# LEDmatrixboardV1_2_4.net
KiCad netlist of a schematic drawn in EAGLE
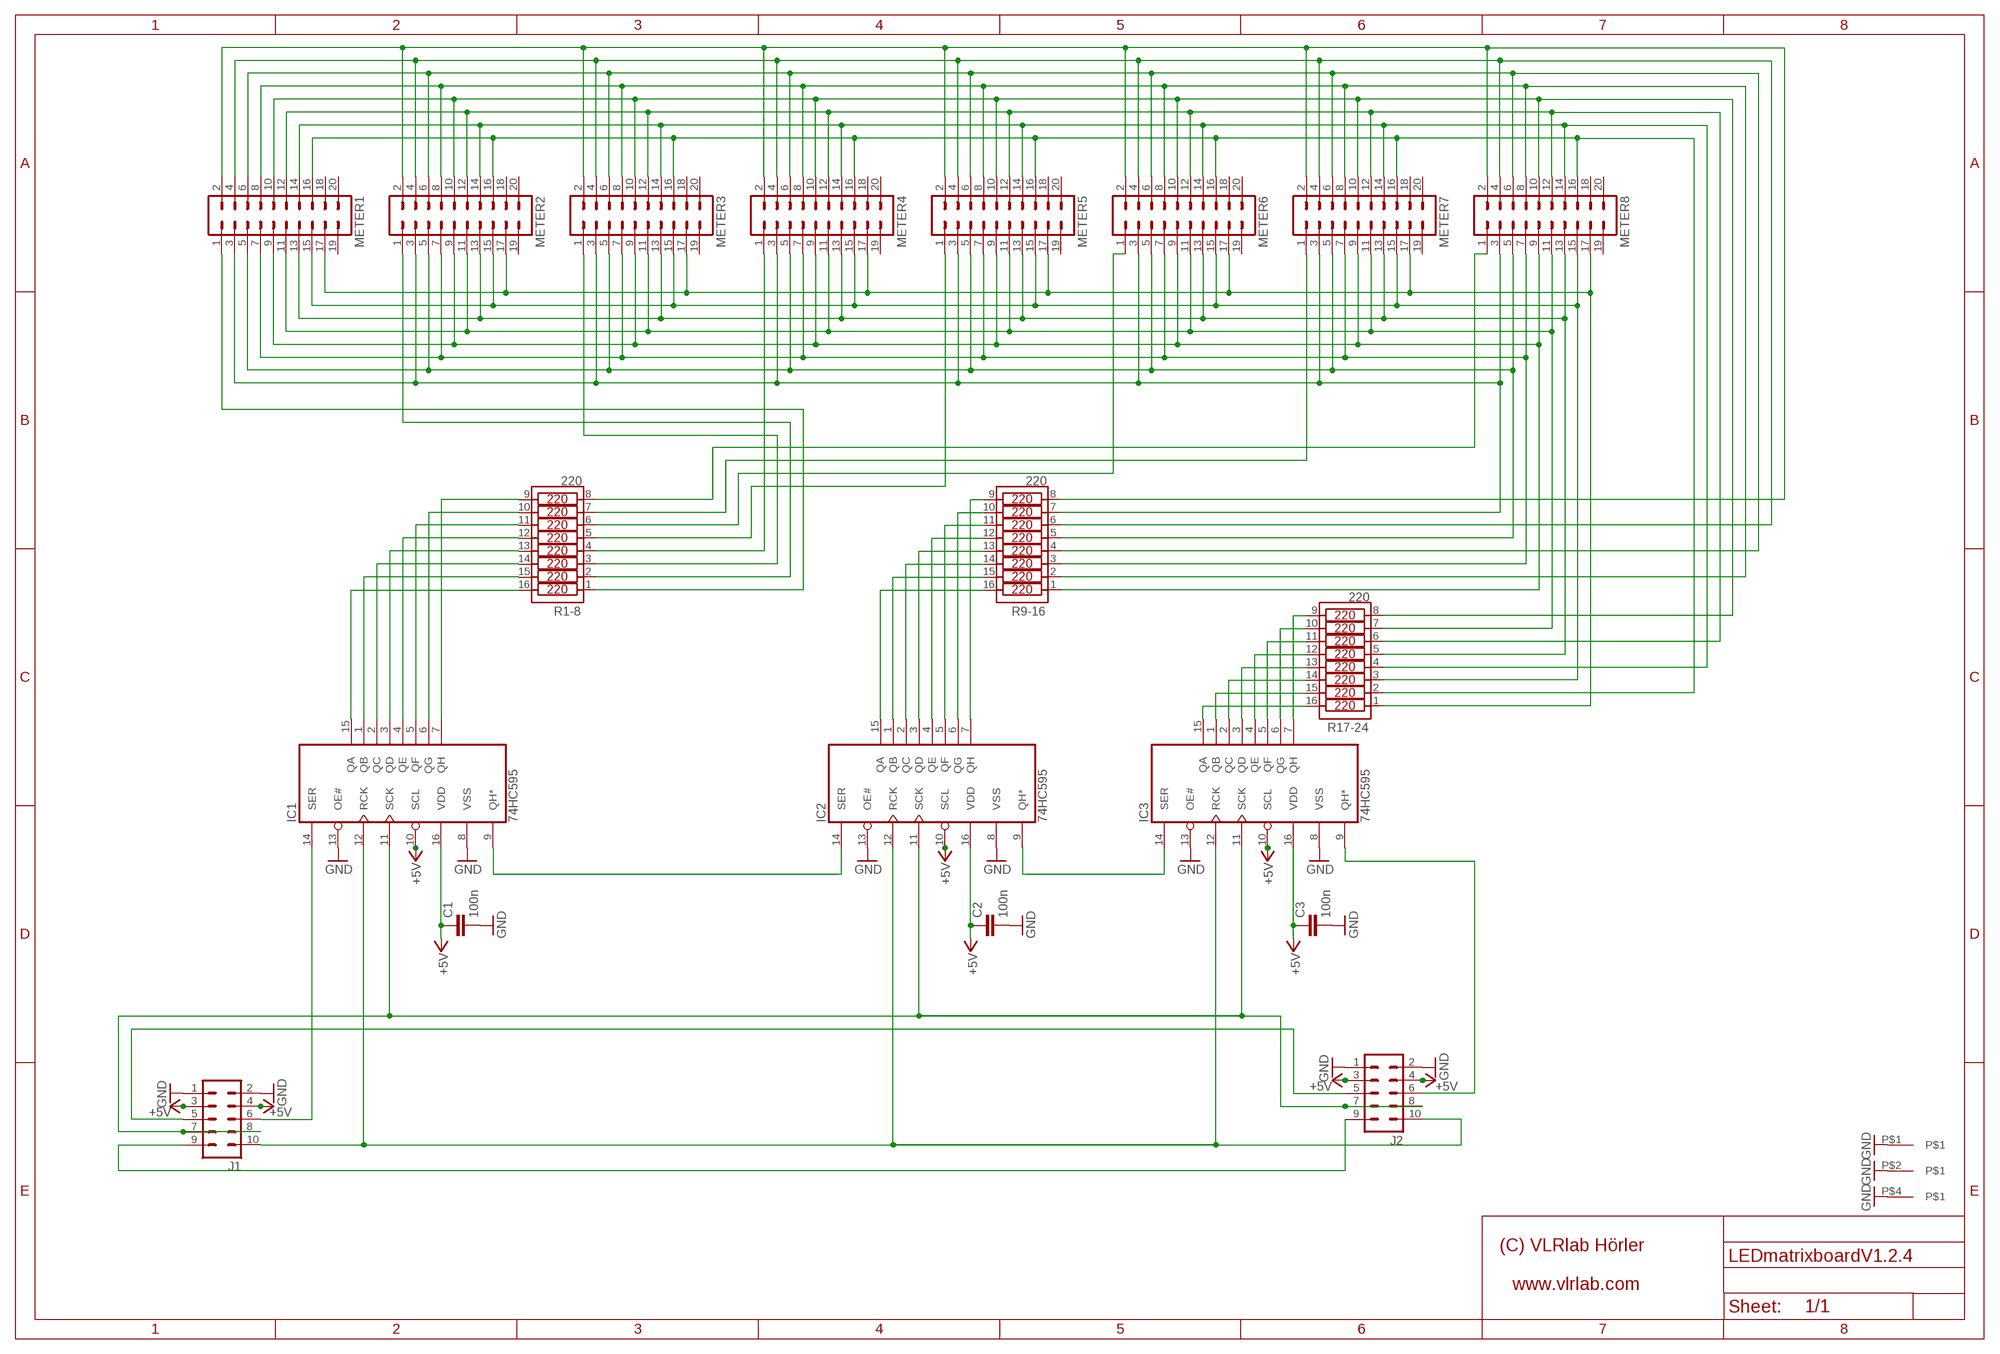
[diagram p0: schematic, sheet 1]

(export (version "E")
  (design (tool "Eeschema 10.0.6"))
  (components
    (comp (ref "C1")
      (value "100n")
      (footprint "eagle-import:C025-030X050")
      (libsource (lib "eagle-import") (part "C-EU025-030X050"))
    )
    (comp (ref "C2")
      (value "100n")
      (footprint "eagle-import:C025-030X050")
      (libsource (lib "eagle-import") (part "C-EU025-030X050"))
    )
    (comp (ref "C3")
      (value "100n")
      (footprint "eagle-import:C025-030X050")
      (libsource (lib "eagle-import") (part "C-EU025-030X050"))
    )
    (comp (ref "IC1")
      (value "74HC595")
      (footprint "eagle-import:SO16D")
      (libsource (lib "eagle-import") (part "595-541-165-uln2803_74HC595SO16D"))
    )
    (comp (ref "IC2")
      (value "74HC595")
      (footprint "eagle-import:SO16D")
      (libsource (lib "eagle-import") (part "595-541-165-uln2803_74HC595SO16D"))
    )
    (comp (ref "IC3")
      (value "74HC595")
      (footprint "eagle-import:SO16D")
      (libsource (lib "eagle-import") (part "595-541-165-uln2803_74HC595SO16D"))
    )
    (comp (ref "J1")
      (value "ML10")
      (footprint "eagle-import:ML10")
      (libsource (lib "eagle-import") (part "ML10"))
    )
    (comp (ref "J2")
      (value "ML10")
      (footprint "eagle-import:ML10")
      (libsource (lib "eagle-import") (part "ML10"))
    )
    (comp (ref "METER1")
      (value "ML20")
      (footprint "eagle-import:ML20")
      (libsource (lib "eagle-import") (part "ML20"))
    )
    (comp (ref "METER2")
      (value "ML20")
      (footprint "eagle-import:ML20")
      (libsource (lib "eagle-import") (part "ML20"))
    )
    (comp (ref "METER3")
      (value "ML20")
      (footprint "eagle-import:ML20")
      (libsource (lib "eagle-import") (part "ML20"))
    )
    (comp (ref "METER4")
      (value "ML20")
      (footprint "eagle-import:ML20")
      (libsource (lib "eagle-import") (part "ML20"))
    )
    (comp (ref "METER5")
      (value "ML20")
      (footprint "eagle-import:ML20")
      (libsource (lib "eagle-import") (part "ML20"))
    )
    (comp (ref "METER6")
      (value "ML20")
      (footprint "eagle-import:ML20")
      (libsource (lib "eagle-import") (part "ML20"))
    )
    (comp (ref "METER7")
      (value "ML20")
      (footprint "eagle-import:ML20")
      (libsource (lib "eagle-import") (part "ML20"))
    )
    (comp (ref "METER8")
      (value "ML20")
      (footprint "eagle-import:ML20")
      (libsource (lib "eagle-import") (part "ML20"))
    )
    (comp (ref "R1-8")
      (value "220")
      (footprint "eagle-import:SOIC16W")
      (libsource (lib "eagle-import") (part "4816P-1SOIC16W"))
    )
    (comp (ref "R9-16")
      (value "220")
      (footprint "eagle-import:SOIC16W")
      (libsource (lib "eagle-import") (part "4816P-1SOIC16W"))
    )
    (comp (ref "R17-24")
      (value "220")
      (footprint "eagle-import:SOIC16W")
      (libsource (lib "eagle-import") (part "4816P-1SOIC16W"))
    )
    (comp (ref "U$2")
      (value "MIDIBOX_HALF")
      (footprint "eagle-import:MIDIBOX14X6")
      (libsource (lib "eagle-import") (part "MIDIBOX_HALF"))
    )
  )
  (nets
    (net (code "1") (name "+5V") (class "Default")
      (node (ref "C1") (pin "1") (pinfunction "1_1") (pintype "passive"))
      (node (ref "C2") (pin "1") (pinfunction "1_1") (pintype "passive"))
      (node (ref "C3") (pin "1") (pinfunction "1_1") (pintype "passive"))
      (node (ref "IC1") (pin "10") (pinfunction "SCL_10") (pintype "input"))
      (node (ref "IC1") (pin "16") (pinfunction "VDD_16") (pintype "power_in"))
      (node (ref "IC2") (pin "10") (pinfunction "SCL_10") (pintype "input"))
      (node (ref "IC2") (pin "16") (pinfunction "VDD_16") (pintype "power_in"))
      (node (ref "IC3") (pin "10") (pinfunction "SCL_10") (pintype "input"))
      (node (ref "IC3") (pin "16") (pinfunction "VDD_16") (pintype "power_in"))
      (node (ref "J1") (pin "3") (pinfunction "3_3") (pintype "passive"))
      (node (ref "J1") (pin "4") (pinfunction "4_4") (pintype "passive"))
      (node (ref "J2") (pin "3") (pinfunction "3_3") (pintype "passive"))
      (node (ref "J2") (pin "4") (pinfunction "4_4") (pintype "passive"))
    )
    (net (code "2") (name "GND") (class "Default")
      (node (ref "C1") (pin "2") (pinfunction "2_2") (pintype "passive"))
      (node (ref "C2") (pin "2") (pinfunction "2_2") (pintype "passive"))
      (node (ref "C3") (pin "2") (pinfunction "2_2") (pintype "passive"))
      (node (ref "IC1") (pin "13") (pinfunction "OE#_13") (pintype "input"))
      (node (ref "IC1") (pin "8") (pinfunction "VSS_8") (pintype "power_in"))
      (node (ref "IC2") (pin "13") (pinfunction "OE#_13") (pintype "input"))
      (node (ref "IC2") (pin "8") (pinfunction "VSS_8") (pintype "power_in"))
      (node (ref "IC3") (pin "13") (pinfunction "OE#_13") (pintype "input"))
      (node (ref "IC3") (pin "8") (pinfunction "VSS_8") (pintype "power_in"))
      (node (ref "J1") (pin "1") (pinfunction "1_1") (pintype "passive"))
      (node (ref "J1") (pin "2") (pinfunction "2_2") (pintype "passive"))
      (node (ref "J2") (pin "1") (pinfunction "1_1") (pintype "passive"))
      (node (ref "J2") (pin "2") (pinfunction "2_2") (pintype "passive"))
      (node (ref "U$2") (pin "P$1") (pinfunction "P$1_P$1") (pintype "bidirectional"))
      (node (ref "U$2") (pin "P$2") (pinfunction "P$1_P$2") (pintype "bidirectional"))
      (node (ref "U$2") (pin "P$4") (pinfunction "P$1_P$4") (pintype "bidirectional"))
    )
    (net (code "3") (name "Net-(IC1-QA)") (class "Default")
      (node (ref "IC1") (pin "15") (pinfunction "QA_15") (pintype "tri_state"))
      (node (ref "R1-8") (pin "16") (pinfunction "P$16_16") (pintype "passive"))
    )
    (net (code "4") (name "Net-(IC1-QB)") (class "Default")
      (node (ref "IC1") (pin "1") (pinfunction "QB_1") (pintype "tri_state"))
      (node (ref "R1-8") (pin "15") (pinfunction "P$15_15") (pintype "passive"))
    )
    (net (code "5") (name "Net-(IC1-QC)") (class "Default")
      (node (ref "IC1") (pin "2") (pinfunction "QC_2") (pintype "tri_state"))
      (node (ref "R1-8") (pin "14") (pinfunction "P$14_14") (pintype "passive"))
    )
    (net (code "6") (name "Net-(IC1-QD)") (class "Default")
      (node (ref "IC1") (pin "3") (pinfunction "QD_3") (pintype "tri_state"))
      (node (ref "R1-8") (pin "13") (pinfunction "P$13_13") (pintype "passive"))
    )
    (net (code "7") (name "Net-(IC1-QE)") (class "Default")
      (node (ref "IC1") (pin "4") (pinfunction "QE_4") (pintype "tri_state"))
      (node (ref "R1-8") (pin "12") (pinfunction "P$12_12") (pintype "passive"))
    )
    (net (code "8") (name "Net-(IC1-QF)") (class "Default")
      (node (ref "IC1") (pin "5") (pinfunction "QF_5") (pintype "tri_state"))
      (node (ref "R1-8") (pin "11") (pinfunction "P$11_11") (pintype "passive"))
    )
    (net (code "9") (name "Net-(IC1-QG)") (class "Default")
      (node (ref "IC1") (pin "6") (pinfunction "QG_6") (pintype "tri_state"))
      (node (ref "R1-8") (pin "10") (pinfunction "P$10_10") (pintype "passive"))
    )
    (net (code "10") (name "Net-(IC1-QH)") (class "Default")
      (node (ref "IC1") (pin "7") (pinfunction "QH_7") (pintype "tri_state"))
      (node (ref "R1-8") (pin "9") (pinfunction "P$9_9") (pintype "passive"))
    )
    (net (code "11") (name "Net-(IC1-QH*)") (class "Default")
      (node (ref "IC1") (pin "9") (pinfunction "QH*_9") (pintype "tri_state"))
      (node (ref "IC2") (pin "14") (pinfunction "SER_14") (pintype "input"))
    )
    (net (code "12") (name "Net-(IC1-RCK)") (class "Default")
      (node (ref "IC1") (pin "12") (pinfunction "RCK_12") (pintype "input"))
      (node (ref "IC2") (pin "12") (pinfunction "RCK_12") (pintype "input"))
      (node (ref "IC3") (pin "12") (pinfunction "RCK_12") (pintype "input"))
      (node (ref "J1") (pin "10") (pinfunction "10_10") (pintype "passive"))
      (node (ref "J2") (pin "10") (pinfunction "10_10") (pintype "passive"))
    )
    (net (code "13") (name "Net-(IC1-SCK)") (class "Default")
      (node (ref "IC1") (pin "11") (pinfunction "SCK_11") (pintype "input"))
      (node (ref "IC2") (pin "11") (pinfunction "SCK_11") (pintype "input"))
      (node (ref "IC3") (pin "11") (pinfunction "SCK_11") (pintype "input"))
      (node (ref "J1") (pin "7") (pinfunction "7_7") (pintype "passive"))
      (node (ref "J1") (pin "8") (pinfunction "8_8") (pintype "passive"))
      (node (ref "J2") (pin "7") (pinfunction "7_7") (pintype "passive"))
      (node (ref "J2") (pin "8") (pinfunction "8_8") (pintype "passive"))
    )
    (net (code "14") (name "Net-(IC1-SER)") (class "Default")
      (node (ref "IC1") (pin "14") (pinfunction "SER_14") (pintype "input"))
      (node (ref "J1") (pin "6") (pinfunction "6_6") (pintype "passive"))
    )
    (net (code "15") (name "Net-(IC2-QA)") (class "Default")
      (node (ref "IC2") (pin "15") (pinfunction "QA_15") (pintype "tri_state"))
      (node (ref "R9-16") (pin "16") (pinfunction "P$16_16") (pintype "passive"))
    )
    (net (code "16") (name "Net-(IC2-QB)") (class "Default")
      (node (ref "IC2") (pin "1") (pinfunction "QB_1") (pintype "tri_state"))
      (node (ref "R9-16") (pin "15") (pinfunction "P$15_15") (pintype "passive"))
    )
    (net (code "17") (name "Net-(IC2-QC)") (class "Default")
      (node (ref "IC2") (pin "2") (pinfunction "QC_2") (pintype "tri_state"))
      (node (ref "R9-16") (pin "14") (pinfunction "P$14_14") (pintype "passive"))
    )
    (net (code "18") (name "Net-(IC2-QD)") (class "Default")
      (node (ref "IC2") (pin "3") (pinfunction "QD_3") (pintype "tri_state"))
      (node (ref "R9-16") (pin "13") (pinfunction "P$13_13") (pintype "passive"))
    )
    (net (code "19") (name "Net-(IC2-QE)") (class "Default")
      (node (ref "IC2") (pin "4") (pinfunction "QE_4") (pintype "tri_state"))
      (node (ref "R9-16") (pin "12") (pinfunction "P$12_12") (pintype "passive"))
    )
    (net (code "20") (name "Net-(IC2-QF)") (class "Default")
      (node (ref "IC2") (pin "5") (pinfunction "QF_5") (pintype "tri_state"))
      (node (ref "R9-16") (pin "11") (pinfunction "P$11_11") (pintype "passive"))
    )
    (net (code "21") (name "Net-(IC2-QG)") (class "Default")
      (node (ref "IC2") (pin "6") (pinfunction "QG_6") (pintype "tri_state"))
      (node (ref "R9-16") (pin "10") (pinfunction "P$10_10") (pintype "passive"))
    )
    (net (code "22") (name "Net-(IC2-QH)") (class "Default")
      (node (ref "IC2") (pin "7") (pinfunction "QH_7") (pintype "tri_state"))
      (node (ref "R9-16") (pin "9") (pinfunction "P$9_9") (pintype "passive"))
    )
    (net (code "23") (name "Net-(IC2-QH*)") (class "Default")
      (node (ref "IC2") (pin "9") (pinfunction "QH*_9") (pintype "tri_state"))
      (node (ref "IC3") (pin "14") (pinfunction "SER_14") (pintype "input"))
    )
    (net (code "24") (name "Net-(IC3-QA)") (class "Default")
      (node (ref "IC3") (pin "15") (pinfunction "QA_15") (pintype "tri_state"))
      (node (ref "R17-24") (pin "16") (pinfunction "P$16_16") (pintype "passive"))
    )
    (net (code "25") (name "Net-(IC3-QB)") (class "Default")
      (node (ref "IC3") (pin "1") (pinfunction "QB_1") (pintype "tri_state"))
      (node (ref "R17-24") (pin "15") (pinfunction "P$15_15") (pintype "passive"))
    )
    (net (code "26") (name "Net-(IC3-QC)") (class "Default")
      (node (ref "IC3") (pin "2") (pinfunction "QC_2") (pintype "tri_state"))
      (node (ref "R17-24") (pin "14") (pinfunction "P$14_14") (pintype "passive"))
    )
    (net (code "27") (name "Net-(IC3-QD)") (class "Default")
      (node (ref "IC3") (pin "3") (pinfunction "QD_3") (pintype "tri_state"))
      (node (ref "R17-24") (pin "13") (pinfunction "P$13_13") (pintype "passive"))
    )
    (net (code "28") (name "Net-(IC3-QE)") (class "Default")
      (node (ref "IC3") (pin "4") (pinfunction "QE_4") (pintype "tri_state"))
      (node (ref "R17-24") (pin "12") (pinfunction "P$12_12") (pintype "passive"))
    )
    (net (code "29") (name "Net-(IC3-QF)") (class "Default")
      (node (ref "IC3") (pin "5") (pinfunction "QF_5") (pintype "tri_state"))
      (node (ref "R17-24") (pin "11") (pinfunction "P$11_11") (pintype "passive"))
    )
    (net (code "30") (name "Net-(IC3-QG)") (class "Default")
      (node (ref "IC3") (pin "6") (pinfunction "QG_6") (pintype "tri_state"))
      (node (ref "R17-24") (pin "10") (pinfunction "P$10_10") (pintype "passive"))
    )
    (net (code "31") (name "Net-(IC3-QH)") (class "Default")
      (node (ref "IC3") (pin "7") (pinfunction "QH_7") (pintype "tri_state"))
      (node (ref "R17-24") (pin "9") (pinfunction "P$9_9") (pintype "passive"))
    )
    (net (code "32") (name "Net-(IC3-QH*)") (class "Default")
      (node (ref "IC3") (pin "9") (pinfunction "QH*_9") (pintype "tri_state"))
      (node (ref "J2") (pin "6") (pinfunction "6_6") (pintype "passive"))
    )
    (net (code "33") (name "Net-(J1-Pad5)") (class "Default")
      (node (ref "J1") (pin "5") (pinfunction "5_5") (pintype "passive"))
      (node (ref "J2") (pin "5") (pinfunction "5_5") (pintype "passive"))
    )
    (net (code "34") (name "Net-(J1-Pad9)") (class "Default")
      (node (ref "J1") (pin "9") (pinfunction "9_9") (pintype "passive"))
      (node (ref "J2") (pin "9") (pinfunction "9_9") (pintype "passive"))
    )
    (net (code "35") (name "Net-(R1-8-P$1)") (class "Default")
      (node (ref "METER1") (pin "1") (pinfunction "1_1") (pintype "passive"))
      (node (ref "R1-8") (pin "1") (pinfunction "P$1_1") (pintype "passive"))
    )
    (net (code "36") (name "Net-(R1-8-P$2)") (class "Default")
      (node (ref "METER2") (pin "1") (pinfunction "1_1") (pintype "passive"))
      (node (ref "R1-8") (pin "2") (pinfunction "P$2_2") (pintype "passive"))
    )
    (net (code "37") (name "Net-(R1-8-P$3)") (class "Default")
      (node (ref "METER3") (pin "1") (pinfunction "1_1") (pintype "passive"))
      (node (ref "R1-8") (pin "3") (pinfunction "P$3_3") (pintype "passive"))
    )
    (net (code "38") (name "Net-(R1-8-P$4)") (class "Default")
      (node (ref "METER4") (pin "1") (pinfunction "1_1") (pintype "passive"))
      (node (ref "R1-8") (pin "4") (pinfunction "P$4_4") (pintype "passive"))
    )
    (net (code "39") (name "Net-(R1-8-P$5)") (class "Default")
      (node (ref "METER5") (pin "1") (pinfunction "1_1") (pintype "passive"))
      (node (ref "R1-8") (pin "5") (pinfunction "P$5_5") (pintype "passive"))
    )
    (net (code "40") (name "Net-(R1-8-P$6)") (class "Default")
      (node (ref "METER6") (pin "1") (pinfunction "1_1") (pintype "passive"))
      (node (ref "R1-8") (pin "6") (pinfunction "P$6_6") (pintype "passive"))
    )
    (net (code "41") (name "Net-(R1-8-P$7)") (class "Default")
      (node (ref "METER7") (pin "1") (pinfunction "1_1") (pintype "passive"))
      (node (ref "R1-8") (pin "7") (pinfunction "P$7_7") (pintype "passive"))
    )
    (net (code "42") (name "Net-(R1-8-P$8)") (class "Default")
      (node (ref "METER8") (pin "1") (pinfunction "1_1") (pintype "passive"))
      (node (ref "R1-8") (pin "8") (pinfunction "P$8_8") (pintype "passive"))
    )
    (net (code "43") (name "Net-(R9-16-P$1)") (class "Default")
      (node (ref "METER1") (pin "9") (pinfunction "9_9") (pintype "passive"))
      (node (ref "METER2") (pin "9") (pinfunction "9_9") (pintype "passive"))
      (node (ref "METER3") (pin "9") (pinfunction "9_9") (pintype "passive"))
      (node (ref "METER4") (pin "9") (pinfunction "9_9") (pintype "passive"))
      (node (ref "METER5") (pin "9") (pinfunction "9_9") (pintype "passive"))
      (node (ref "METER6") (pin "9") (pinfunction "9_9") (pintype "passive"))
      (node (ref "METER7") (pin "9") (pinfunction "9_9") (pintype "passive"))
      (node (ref "METER8") (pin "9") (pinfunction "9_9") (pintype "passive"))
      (node (ref "R9-16") (pin "1") (pinfunction "P$1_1") (pintype "passive"))
    )
    (net (code "44") (name "Net-(R9-16-P$2)") (class "Default")
      (node (ref "METER1") (pin "8") (pinfunction "8_8") (pintype "passive"))
      (node (ref "METER2") (pin "8") (pinfunction "8_8") (pintype "passive"))
      (node (ref "METER3") (pin "8") (pinfunction "8_8") (pintype "passive"))
      (node (ref "METER4") (pin "8") (pinfunction "8_8") (pintype "passive"))
      (node (ref "METER5") (pin "8") (pinfunction "8_8") (pintype "passive"))
      (node (ref "METER6") (pin "8") (pinfunction "8_8") (pintype "passive"))
      (node (ref "METER7") (pin "8") (pinfunction "8_8") (pintype "passive"))
      (node (ref "METER8") (pin "8") (pinfunction "8_8") (pintype "passive"))
      (node (ref "R9-16") (pin "2") (pinfunction "P$2_2") (pintype "passive"))
    )
    (net (code "45") (name "Net-(R9-16-P$3)") (class "Default")
      (node (ref "METER1") (pin "7") (pinfunction "7_7") (pintype "passive"))
      (node (ref "METER2") (pin "7") (pinfunction "7_7") (pintype "passive"))
      (node (ref "METER3") (pin "7") (pinfunction "7_7") (pintype "passive"))
      (node (ref "METER4") (pin "7") (pinfunction "7_7") (pintype "passive"))
      (node (ref "METER5") (pin "7") (pinfunction "7_7") (pintype "passive"))
      (node (ref "METER6") (pin "7") (pinfunction "7_7") (pintype "passive"))
      (node (ref "METER7") (pin "7") (pinfunction "7_7") (pintype "passive"))
      (node (ref "METER8") (pin "7") (pinfunction "7_7") (pintype "passive"))
      (node (ref "R9-16") (pin "3") (pinfunction "P$3_3") (pintype "passive"))
    )
    (net (code "46") (name "Net-(R9-16-P$4)") (class "Default")
      (node (ref "METER1") (pin "6") (pinfunction "6_6") (pintype "passive"))
      (node (ref "METER2") (pin "6") (pinfunction "6_6") (pintype "passive"))
      (node (ref "METER3") (pin "6") (pinfunction "6_6") (pintype "passive"))
      (node (ref "METER4") (pin "6") (pinfunction "6_6") (pintype "passive"))
      (node (ref "METER5") (pin "6") (pinfunction "6_6") (pintype "passive"))
      (node (ref "METER6") (pin "6") (pinfunction "6_6") (pintype "passive"))
      (node (ref "METER7") (pin "6") (pinfunction "6_6") (pintype "passive"))
      (node (ref "METER8") (pin "6") (pinfunction "6_6") (pintype "passive"))
      (node (ref "R9-16") (pin "4") (pinfunction "P$4_4") (pintype "passive"))
    )
    (net (code "47") (name "Net-(R9-16-P$5)") (class "Default")
      (node (ref "METER1") (pin "5") (pinfunction "5_5") (pintype "passive"))
      (node (ref "METER2") (pin "5") (pinfunction "5_5") (pintype "passive"))
      (node (ref "METER3") (pin "5") (pinfunction "5_5") (pintype "passive"))
      (node (ref "METER4") (pin "5") (pinfunction "5_5") (pintype "passive"))
      (node (ref "METER5") (pin "5") (pinfunction "5_5") (pintype "passive"))
      (node (ref "METER6") (pin "5") (pinfunction "5_5") (pintype "passive"))
      (node (ref "METER7") (pin "5") (pinfunction "5_5") (pintype "passive"))
      (node (ref "METER8") (pin "5") (pinfunction "5_5") (pintype "passive"))
      (node (ref "R9-16") (pin "5") (pinfunction "P$5_5") (pintype "passive"))
    )
    (net (code "48") (name "Net-(R9-16-P$6)") (class "Default")
      (node (ref "METER1") (pin "4") (pinfunction "4_4") (pintype "passive"))
      (node (ref "METER2") (pin "4") (pinfunction "4_4") (pintype "passive"))
      (node (ref "METER3") (pin "4") (pinfunction "4_4") (pintype "passive"))
      (node (ref "METER4") (pin "4") (pinfunction "4_4") (pintype "passive"))
      (node (ref "METER5") (pin "4") (pinfunction "4_4") (pintype "passive"))
      (node (ref "METER6") (pin "4") (pinfunction "4_4") (pintype "passive"))
      (node (ref "METER7") (pin "4") (pinfunction "4_4") (pintype "passive"))
      (node (ref "METER8") (pin "4") (pinfunction "4_4") (pintype "passive"))
      (node (ref "R9-16") (pin "6") (pinfunction "P$6_6") (pintype "passive"))
    )
    (net (code "49") (name "Net-(R9-16-P$7)") (class "Default")
      (node (ref "METER1") (pin "3") (pinfunction "3_3") (pintype "passive"))
      (node (ref "METER2") (pin "3") (pinfunction "3_3") (pintype "passive"))
      (node (ref "METER3") (pin "3") (pinfunction "3_3") (pintype "passive"))
      (node (ref "METER4") (pin "3") (pinfunction "3_3") (pintype "passive"))
      (node (ref "METER5") (pin "3") (pinfunction "3_3") (pintype "passive"))
      (node (ref "METER6") (pin "3") (pinfunction "3_3") (pintype "passive"))
      (node (ref "METER7") (pin "3") (pinfunction "3_3") (pintype "passive"))
      (node (ref "METER8") (pin "3") (pinfunction "3_3") (pintype "passive"))
      (node (ref "R9-16") (pin "7") (pinfunction "P$7_7") (pintype "passive"))
    )
    (net (code "50") (name "Net-(R9-16-P$8)") (class "Default")
      (node (ref "METER1") (pin "2") (pinfunction "2_2") (pintype "passive"))
      (node (ref "METER2") (pin "2") (pinfunction "2_2") (pintype "passive"))
      (node (ref "METER3") (pin "2") (pinfunction "2_2") (pintype "passive"))
      (node (ref "METER4") (pin "2") (pinfunction "2_2") (pintype "passive"))
      (node (ref "METER5") (pin "2") (pinfunction "2_2") (pintype "passive"))
      (node (ref "METER6") (pin "2") (pinfunction "2_2") (pintype "passive"))
      (node (ref "METER7") (pin "2") (pinfunction "2_2") (pintype "passive"))
      (node (ref "METER8") (pin "2") (pinfunction "2_2") (pintype "passive"))
      (node (ref "R9-16") (pin "8") (pinfunction "P$8_8") (pintype "passive"))
    )
    (net (code "51") (name "Net-(R17-24-P$1)") (class "Default")
      (node (ref "METER1") (pin "17") (pinfunction "17_17") (pintype "passive"))
      (node (ref "METER2") (pin "17") (pinfunction "17_17") (pintype "passive"))
      (node (ref "METER3") (pin "17") (pinfunction "17_17") (pintype "passive"))
      (node (ref "METER4") (pin "17") (pinfunction "17_17") (pintype "passive"))
      (node (ref "METER5") (pin "17") (pinfunction "17_17") (pintype "passive"))
      (node (ref "METER6") (pin "17") (pinfunction "17_17") (pintype "passive"))
      (node (ref "METER7") (pin "17") (pinfunction "17_17") (pintype "passive"))
      (node (ref "METER8") (pin "17") (pinfunction "17_17") (pintype "passive"))
      (node (ref "R17-24") (pin "1") (pinfunction "P$1_1") (pintype "passive"))
    )
    (net (code "52") (name "Net-(R17-24-P$2)") (class "Default")
      (node (ref "METER1") (pin "16") (pinfunction "16_16") (pintype "passive"))
      (node (ref "METER2") (pin "16") (pinfunction "16_16") (pintype "passive"))
      (node (ref "METER3") (pin "16") (pinfunction "16_16") (pintype "passive"))
      (node (ref "METER4") (pin "16") (pinfunction "16_16") (pintype "passive"))
      (node (ref "METER5") (pin "16") (pinfunction "16_16") (pintype "passive"))
      (node (ref "METER6") (pin "16") (pinfunction "16_16") (pintype "passive"))
      (node (ref "METER7") (pin "16") (pinfunction "16_16") (pintype "passive"))
      (node (ref "METER8") (pin "16") (pinfunction "16_16") (pintype "passive"))
      (node (ref "R17-24") (pin "2") (pinfunction "P$2_2") (pintype "passive"))
    )
    (net (code "53") (name "Net-(R17-24-P$3)") (class "Default")
      (node (ref "METER1") (pin "15") (pinfunction "15_15") (pintype "passive"))
      (node (ref "METER2") (pin "15") (pinfunction "15_15") (pintype "passive"))
      (node (ref "METER3") (pin "15") (pinfunction "15_15") (pintype "passive"))
      (node (ref "METER4") (pin "15") (pinfunction "15_15") (pintype "passive"))
      (node (ref "METER5") (pin "15") (pinfunction "15_15") (pintype "passive"))
      (node (ref "METER6") (pin "15") (pinfunction "15_15") (pintype "passive"))
      (node (ref "METER7") (pin "15") (pinfunction "15_15") (pintype "passive"))
      (node (ref "METER8") (pin "15") (pinfunction "15_15") (pintype "passive"))
      (node (ref "R17-24") (pin "3") (pinfunction "P$3_3") (pintype "passive"))
    )
    (net (code "54") (name "Net-(R17-24-P$4)") (class "Default")
      (node (ref "METER1") (pin "14") (pinfunction "14_14") (pintype "passive"))
      (node (ref "METER2") (pin "14") (pinfunction "14_14") (pintype "passive"))
      (node (ref "METER3") (pin "14") (pinfunction "14_14") (pintype "passive"))
      (node (ref "METER4") (pin "14") (pinfunction "14_14") (pintype "passive"))
      (node (ref "METER5") (pin "14") (pinfunction "14_14") (pintype "passive"))
      (node (ref "METER6") (pin "14") (pinfunction "14_14") (pintype "passive"))
      (node (ref "METER7") (pin "14") (pinfunction "14_14") (pintype "passive"))
      (node (ref "METER8") (pin "14") (pinfunction "14_14") (pintype "passive"))
      (node (ref "R17-24") (pin "4") (pinfunction "P$4_4") (pintype "passive"))
    )
    (net (code "55") (name "Net-(R17-24-P$5)") (class "Default")
      (node (ref "METER1") (pin "13") (pinfunction "13_13") (pintype "passive"))
      (node (ref "METER2") (pin "13") (pinfunction "13_13") (pintype "passive"))
      (node (ref "METER3") (pin "13") (pinfunction "13_13") (pintype "passive"))
      (node (ref "METER4") (pin "13") (pinfunction "13_13") (pintype "passive"))
      (node (ref "METER5") (pin "13") (pinfunction "13_13") (pintype "passive"))
      (node (ref "METER6") (pin "13") (pinfunction "13_13") (pintype "passive"))
      (node (ref "METER7") (pin "13") (pinfunction "13_13") (pintype "passive"))
      (node (ref "METER8") (pin "13") (pinfunction "13_13") (pintype "passive"))
      (node (ref "R17-24") (pin "5") (pinfunction "P$5_5") (pintype "passive"))
    )
    (net (code "56") (name "Net-(R17-24-P$6)") (class "Default")
      (node (ref "METER1") (pin "12") (pinfunction "12_12") (pintype "passive"))
      (node (ref "METER2") (pin "12") (pinfunction "12_12") (pintype "passive"))
      (node (ref "METER3") (pin "12") (pinfunction "12_12") (pintype "passive"))
      (node (ref "METER4") (pin "12") (pinfunction "12_12") (pintype "passive"))
      (node (ref "METER5") (pin "12") (pinfunction "12_12") (pintype "passive"))
      (node (ref "METER6") (pin "12") (pinfunction "12_12") (pintype "passive"))
      (node (ref "METER7") (pin "12") (pinfunction "12_12") (pintype "passive"))
      (node (ref "METER8") (pin "12") (pinfunction "12_12") (pintype "passive"))
      (node (ref "R17-24") (pin "6") (pinfunction "P$6_6") (pintype "passive"))
    )
    (net (code "57") (name "Net-(R17-24-P$7)") (class "Default")
      (node (ref "METER1") (pin "11") (pinfunction "11_11") (pintype "passive"))
      (node (ref "METER2") (pin "11") (pinfunction "11_11") (pintype "passive"))
      (node (ref "METER3") (pin "11") (pinfunction "11_11") (pintype "passive"))
      (node (ref "METER4") (pin "11") (pinfunction "11_11") (pintype "passive"))
      (node (ref "METER5") (pin "11") (pinfunction "11_11") (pintype "passive"))
      (node (ref "METER6") (pin "11") (pinfunction "11_11") (pintype "passive"))
      (node (ref "METER7") (pin "11") (pinfunction "11_11") (pintype "passive"))
      (node (ref "METER8") (pin "11") (pinfunction "11_11") (pintype "passive"))
      (node (ref "R17-24") (pin "7") (pinfunction "P$7_7") (pintype "passive"))
    )
    (net (code "58") (name "Net-(R17-24-P$8)") (class "Default")
      (node (ref "METER1") (pin "10") (pinfunction "10_10") (pintype "passive"))
      (node (ref "METER2") (pin "10") (pinfunction "10_10") (pintype "passive"))
      (node (ref "METER3") (pin "10") (pinfunction "10_10") (pintype "passive"))
      (node (ref "METER4") (pin "10") (pinfunction "10_10") (pintype "passive"))
      (node (ref "METER5") (pin "10") (pinfunction "10_10") (pintype "passive"))
      (node (ref "METER6") (pin "10") (pinfunction "10_10") (pintype "passive"))
      (node (ref "METER7") (pin "10") (pinfunction "10_10") (pintype "passive"))
      (node (ref "METER8") (pin "10") (pinfunction "10_10") (pintype "passive"))
      (node (ref "R17-24") (pin "8") (pinfunction "P$8_8") (pintype "passive"))
    )
    (net (code "59") (name "unconnected-(METER1-Pad18)") (class "Default")
      (node (ref "METER1") (pin "18") (pinfunction "18_18") (pintype "passive"))
    )
    (net (code "60") (name "unconnected-(METER1-Pad19)") (class "Default")
      (node (ref "METER1") (pin "19") (pinfunction "19_19") (pintype "passive"))
    )
    (net (code "61") (name "unconnected-(METER1-Pad20)") (class "Default")
      (node (ref "METER1") (pin "20") (pinfunction "20_20") (pintype "passive"))
    )
    (net (code "62") (name "unconnected-(METER2-Pad18)") (class "Default")
      (node (ref "METER2") (pin "18") (pinfunction "18_18") (pintype "passive"))
    )
    (net (code "63") (name "unconnected-(METER2-Pad19)") (class "Default")
      (node (ref "METER2") (pin "19") (pinfunction "19_19") (pintype "passive"))
    )
    (net (code "64") (name "unconnected-(METER2-Pad20)") (class "Default")
      (node (ref "METER2") (pin "20") (pinfunction "20_20") (pintype "passive"))
    )
    (net (code "65") (name "unconnected-(METER3-Pad18)") (class "Default")
      (node (ref "METER3") (pin "18") (pinfunction "18_18") (pintype "passive"))
    )
    (net (code "66") (name "unconnected-(METER3-Pad19)") (class "Default")
      (node (ref "METER3") (pin "19") (pinfunction "19_19") (pintype "passive"))
    )
    (net (code "67") (name "unconnected-(METER3-Pad20)") (class "Default")
      (node (ref "METER3") (pin "20") (pinfunction "20_20") (pintype "passive"))
    )
    (net (code "68") (name "unconnected-(METER4-Pad18)") (class "Default")
      (node (ref "METER4") (pin "18") (pinfunction "18_18") (pintype "passive"))
    )
    (net (code "69") (name "unconnected-(METER4-Pad19)") (class "Default")
      (node (ref "METER4") (pin "19") (pinfunction "19_19") (pintype "passive"))
    )
    (net (code "70") (name "unconnected-(METER4-Pad20)") (class "Default")
      (node (ref "METER4") (pin "20") (pinfunction "20_20") (pintype "passive"))
    )
    (net (code "71") (name "unconnected-(METER5-Pad18)") (class "Default")
      (node (ref "METER5") (pin "18") (pinfunction "18_18") (pintype "passive"))
    )
    (net (code "72") (name "unconnected-(METER5-Pad19)") (class "Default")
      (node (ref "METER5") (pin "19") (pinfunction "19_19") (pintype "passive"))
    )
    (net (code "73") (name "unconnected-(METER5-Pad20)") (class "Default")
      (node (ref "METER5") (pin "20") (pinfunction "20_20") (pintype "passive"))
    )
    (net (code "74") (name "unconnected-(METER6-Pad18)") (class "Default")
      (node (ref "METER6") (pin "18") (pinfunction "18_18") (pintype "passive"))
    )
    (net (code "75") (name "unconnected-(METER6-Pad19)") (class "Default")
      (node (ref "METER6") (pin "19") (pinfunction "19_19") (pintype "passive"))
    )
    (net (code "76") (name "unconnected-(METER6-Pad20)") (class "Default")
      (node (ref "METER6") (pin "20") (pinfunction "20_20") (pintype "passive"))
    )
    (net (code "77") (name "unconnected-(METER7-Pad18)") (class "Default")
      (node (ref "METER7") (pin "18") (pinfunction "18_18") (pintype "passive"))
    )
    (net (code "78") (name "unconnected-(METER7-Pad19)") (class "Default")
      (node (ref "METER7") (pin "19") (pinfunction "19_19") (pintype "passive"))
    )
    (net (code "79") (name "unconnected-(METER7-Pad20)") (class "Default")
      (node (ref "METER7") (pin "20") (pinfunction "20_20") (pintype "passive"))
    )
    (net (code "80") (name "unconnected-(METER8-Pad18)") (class "Default")
      (node (ref "METER8") (pin "18") (pinfunction "18_18") (pintype "passive"))
    )
    (net (code "81") (name "unconnected-(METER8-Pad19)") (class "Default")
      (node (ref "METER8") (pin "19") (pinfunction "19_19") (pintype "passive"))
    )
    (net (code "82") (name "unconnected-(METER8-Pad20)") (class "Default")
      (node (ref "METER8") (pin "20") (pinfunction "20_20") (pintype "passive"))
    )
  )
)
